# I2C_GPIOs_MIPI-CSI.net
KiCad netlist of a schematic drawn in Altium Designer
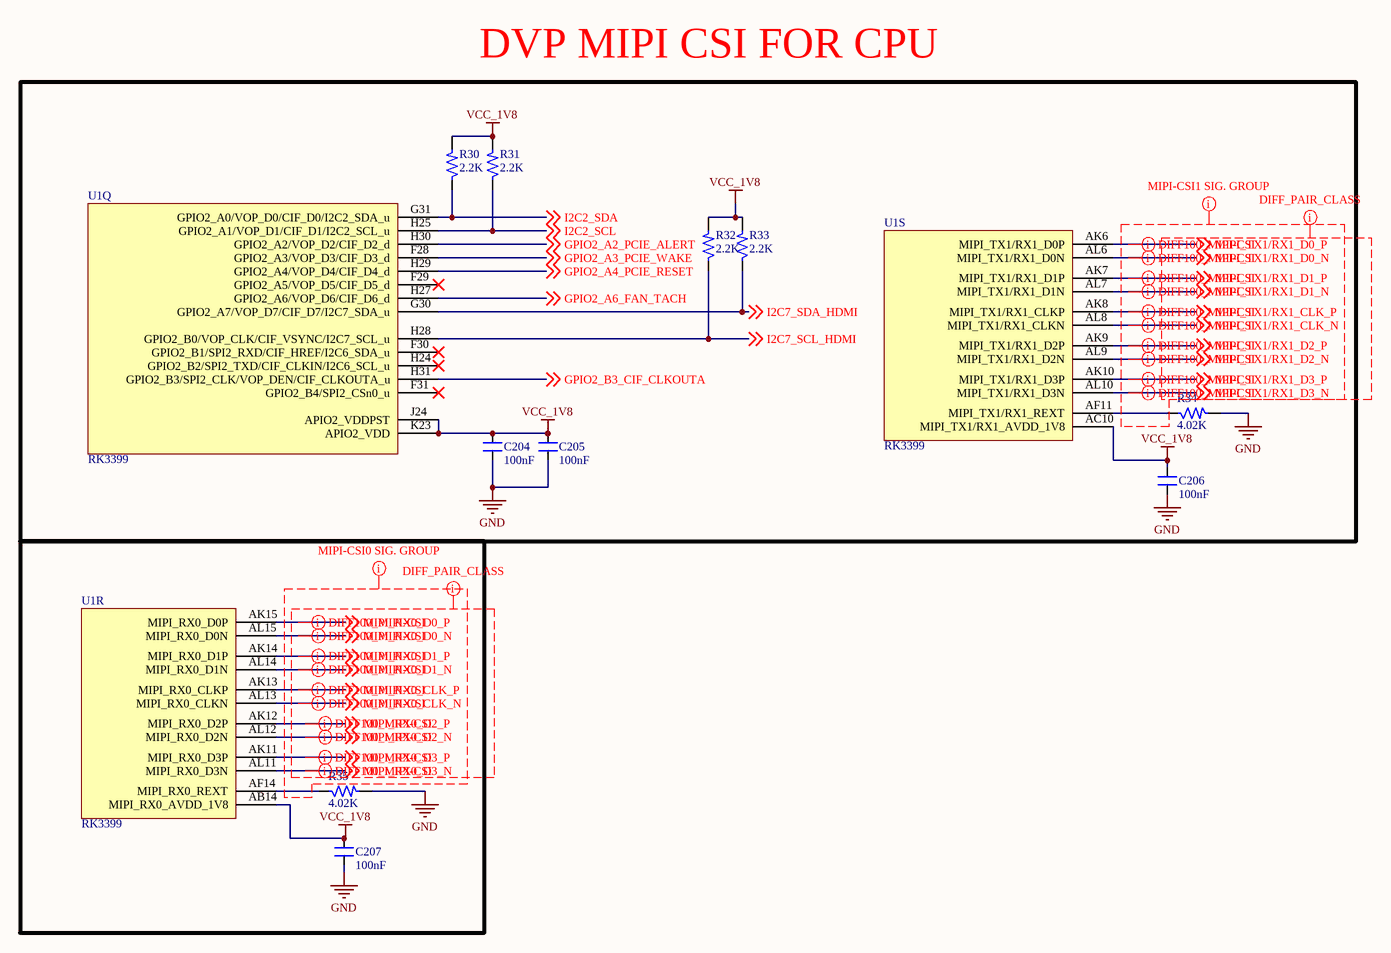
[diagram p0: I2C_GPIOs_MIPI-CSI.SchDoc]

(export (version "E")
  (design (tool "Eeschema 10.0.6"))
  (components
    (comp (ref "C204")
      (value "100nF")
      (footprint "CAP_0201")
      (description "0.1µF ±10% 25V Ceramic Capacitor X5R 0201 (0603 Metric)")
      (fields
        (field (name "MANUFACTURER") "TDK Corporation")
        (field (name "MANUFACTURER PART NUMBER") "C0603X5R1E104K030BB")
      )
      (libsource (lib "RK3399 _Module_Intlib") (part "CAP_100nF-25V-10%-0201"))
    )
    (comp (ref "C205")
      (value "100nF")
      (footprint "CAP_0201")
      (description "0.1µF ±10% 25V Ceramic Capacitor X5R 0201 (0603 Metric)")
      (fields
        (field (name "MANUFACTURER") "TDK Corporation")
        (field (name "MANUFACTURER PART NUMBER") "C0603X5R1E104K030BB")
      )
      (libsource (lib "RK3399 _Module_Intlib") (part "CAP_100nF-25V-10%-0201"))
    )
    (comp (ref "C206")
      (value "100nF")
      (footprint "CAP_0201")
      (description "0.1µF ±10% 25V Ceramic Capacitor X5R 0201 (0603 Metric)")
      (fields
        (field (name "MANUFACTURER") "TDK Corporation")
        (field (name "MANUFACTURER PART NUMBER") "C0603X5R1E104K030BB")
      )
      (libsource (lib "RK3399 _Module_Intlib") (part "CAP_100nF-25V-10%-0201"))
    )
    (comp (ref "C207")
      (value "100nF")
      (footprint "CAP_0201")
      (description "0.1µF ±10% 25V Ceramic Capacitor X5R 0201 (0603 Metric)")
      (fields
        (field (name "MANUFACTURER") "TDK Corporation")
        (field (name "MANUFACTURER PART NUMBER") "C0603X5R1E104K030BB")
      )
      (libsource (lib "RK3399 _Module_Intlib") (part "CAP_100nF-25V-10%-0201"))
    )
    (comp (ref "R30")
      (value "2.2K")
      (footprint "RES_0201")
      (description "2.2 kOhms ±1% 0.05W, 1/20W Chip Resistor 0201 (0603 Metric) Thick Film")
      (fields
        (field (name "MANUFACTURER") "Stackpole Electronics Inc")
        (field (name "MANUFACTURER PART NUMBER") "RMCF0201FT2K20")
      )
      (libsource (lib "RK3399 _Module_Intlib") (part "RES_2.2K-0.05W-1%-0201"))
    )
    (comp (ref "R31")
      (value "2.2K")
      (footprint "RES_0201")
      (description "2.2 kOhms ±1% 0.05W, 1/20W Chip Resistor 0201 (0603 Metric) Thick Film")
      (fields
        (field (name "MANUFACTURER") "Stackpole Electronics Inc")
        (field (name "MANUFACTURER PART NUMBER") "RMCF0201FT2K20")
      )
      (libsource (lib "RK3399 _Module_Intlib") (part "RES_2.2K-0.05W-1%-0201"))
    )
    (comp (ref "R32")
      (value "2.2K")
      (footprint "RES_0201")
      (description "2.2 kOhms ±1% 0.05W, 1/20W Chip Resistor 0201 (0603 Metric) Thick Film")
      (fields
        (field (name "MANUFACTURER") "Stackpole Electronics Inc")
        (field (name "MANUFACTURER PART NUMBER") "RMCF0201FT2K20")
      )
      (libsource (lib "RK3399 _Module_Intlib") (part "RES_2.2K-0.05W-1%-0201"))
    )
    (comp (ref "R33")
      (value "2.2K")
      (footprint "RES_0201")
      (description "2.2 kOhms ±1% 0.05W, 1/20W Chip Resistor 0201 (0603 Metric) Thick Film")
      (fields
        (field (name "MANUFACTURER") "Stackpole Electronics Inc")
        (field (name "MANUFACTURER PART NUMBER") "RMCF0201FT2K20")
      )
      (libsource (lib "RK3399 _Module_Intlib") (part "RES_2.2K-0.05W-1%-0201"))
    )
    (comp (ref "R34")
      (value "4.02K")
      (footprint "RES_0201")
      (description "4.02 kOhms ±1% 0.05W, 1/20W Chip Resistor 0201 (0603 Metric) Thick Film")
      (fields
        (field (name "MANUFACTURER") "Yageo")
        (field (name "MANUFACTURER PART NUMBER") "RC0201FR-074K02L")
      )
      (libsource (lib "RK3399 _Module_Intlib") (part "RES_4.02K-0.05W-1%-0201"))
    )
    (comp (ref "R35")
      (value "4.02K")
      (footprint "RES_0201")
      (description "4.02 kOhms ±1% 0.05W, 1/20W Chip Resistor 0201 (0603 Metric) Thick Film")
      (fields
        (field (name "MANUFACTURER") "Yageo")
        (field (name "MANUFACTURER PART NUMBER") "RC0201FR-074K02L")
      )
      (libsource (lib "RK3399 _Module_Intlib") (part "RES_4.02K-0.05W-1%-0201"))
    )
    (comp (ref "U1")
      (value "RK3399")
      (footprint "FBGA828_23_826X826")
      (description "RK3399 is a low power, high performance processor for computing, personal mobile.")
      (fields (field (name "MANUFACTURER") "Rockchip"))
      (libsource (lib "RK3399 _Module_Schlib") (part "IC_RK3399-FCBGA828"))
    )
  )
  (nets
    (net (code "1") (name "GND") (class "Default")
      (node (ref "C204") (pin "1") (pinfunction "1_1") (pintype "passive"))
      (node (ref "C205") (pin "1") (pinfunction "1_1") (pintype "passive"))
      (node (ref "C206") (pin "1") (pinfunction "1_1") (pintype "passive"))
      (node (ref "C207") (pin "1") (pinfunction "1_1") (pintype "passive"))
      (node (ref "R34") (pin "2") (pinfunction "2_2") (pintype "passive"))
      (node (ref "R35") (pin "2") (pinfunction "2_2") (pintype "passive"))
    )
    (net (code "2") (name "GPIO2_A2_PCIE_ALERT") (class "Default")
      (node (ref "U1") (pin "H30") (pinfunction "GPIO2_A2/VOP_D2/CIF_D2_d_H30") (pintype "passive"))
    )
    (net (code "3") (name "GPIO2_A3_PCIE_WAKE") (class "Default")
      (node (ref "U1") (pin "F28") (pinfunction "GPIO2_A3/VOP_D3/CIF_D3_d_F28") (pintype "passive"))
    )
    (net (code "4") (name "GPIO2_A4_PCIE_RESET") (class "Default")
      (node (ref "U1") (pin "H29") (pinfunction "GPIO2_A4/VOP_D4/CIF_D4_d_H29") (pintype "passive"))
    )
    (net (code "5") (name "GPIO2_A6_FAN_TACH") (class "Default")
      (node (ref "U1") (pin "H27") (pinfunction "GPIO2_A6/VOP_D6/CIF_D6_d_H27") (pintype "passive"))
    )
    (net (code "6") (name "GPIO2_B3_CIF_CLKOUTA") (class "Default")
      (node (ref "U1") (pin "H31") (pinfunction "GPIO2_B3/SPI2_CLK/VOP_DEN/CIF_CLKOUTA_u_H31") (pintype "passive"))
    )
    (net (code "7") (name "I2C2_SCL") (class "Default")
      (node (ref "R31") (pin "1") (pinfunction "1_1") (pintype "passive"))
      (node (ref "U1") (pin "H25") (pinfunction "GPIO2_A1/VOP_D1/CIF_D1/I2C2_SCL_u_H25") (pintype "passive"))
    )
    (net (code "8") (name "I2C2_SDA") (class "Default")
      (node (ref "R30") (pin "1") (pinfunction "1_1") (pintype "passive"))
      (node (ref "U1") (pin "G31") (pinfunction "GPIO2_A0/VOP_D0/CIF_D0/I2C2_SDA_u_G31") (pintype "passive"))
    )
    (net (code "9") (name "I2C7_SCL_HDMI") (class "Default")
      (node (ref "R32") (pin "1") (pinfunction "1_1") (pintype "passive"))
      (node (ref "U1") (pin "H28") (pinfunction "GPIO2_B0/VOP_CLK/CIF_VSYNC/I2C7_SCL_u_H28") (pintype "passive"))
    )
    (net (code "10") (name "I2C7_SDA_HDMI") (class "Default")
      (node (ref "R33") (pin "1") (pinfunction "1_1") (pintype "passive"))
      (node (ref "U1") (pin "G30") (pinfunction "GPIO2_A7/VOP_D7/CIF_D7/I2C7_SDA_u_G30") (pintype "passive"))
    )
    (net (code "11") (name "MIPI_RX0_CLK_N") (class "Default")
      (node (ref "U1") (pin "AL13") (pinfunction "MIPI_RX0_CLKN_AL13") (pintype "passive"))
    )
    (net (code "12") (name "MIPI_RX0_CLK_P") (class "Default")
      (node (ref "U1") (pin "AK13") (pinfunction "MIPI_RX0_CLKP_AK13") (pintype "passive"))
    )
    (net (code "13") (name "MIPI_RX0_D0_N") (class "Default")
      (node (ref "U1") (pin "AL15") (pinfunction "MIPI_RX0_D0N_AL15") (pintype "passive"))
    )
    (net (code "14") (name "MIPI_RX0_D0_P") (class "Default")
      (node (ref "U1") (pin "AK15") (pinfunction "MIPI_RX0_D0P_AK15") (pintype "passive"))
    )
    (net (code "15") (name "MIPI_RX0_D1_N") (class "Default")
      (node (ref "U1") (pin "AL14") (pinfunction "MIPI_RX0_D1N_AL14") (pintype "passive"))
    )
    (net (code "16") (name "MIPI_RX0_D1_P") (class "Default")
      (node (ref "U1") (pin "AK14") (pinfunction "MIPI_RX0_D1P_AK14") (pintype "passive"))
    )
    (net (code "17") (name "MIPI_RX0_D2_N") (class "Default")
      (node (ref "U1") (pin "AL12") (pinfunction "MIPI_RX0_D2N_AL12") (pintype "passive"))
    )
    (net (code "18") (name "MIPI_RX0_D2_P") (class "Default")
      (node (ref "U1") (pin "AK12") (pinfunction "MIPI_RX0_D2P_AK12") (pintype "passive"))
    )
    (net (code "19") (name "MIPI_RX0_D3_N") (class "Default")
      (node (ref "U1") (pin "AL11") (pinfunction "MIPI_RX0_D3N_AL11") (pintype "passive"))
    )
    (net (code "20") (name "MIPI_RX0_D3_P") (class "Default")
      (node (ref "U1") (pin "AK11") (pinfunction "MIPI_RX0_D3P_AK11") (pintype "passive"))
    )
    (net (code "21") (name "MIPI_TX1{slash}RX1_CLK_N") (class "Default")
      (node (ref "U1") (pin "AL8") (pinfunction "MIPI_TX1/RX1_CLKN_AL8") (pintype "passive"))
    )
    (net (code "22") (name "MIPI_TX1{slash}RX1_CLK_P") (class "Default")
      (node (ref "U1") (pin "AK8") (pinfunction "MIPI_TX1/RX1_CLKP_AK8") (pintype "passive"))
    )
    (net (code "23") (name "MIPI_TX1{slash}RX1_D0_N") (class "Default")
      (node (ref "U1") (pin "AL6") (pinfunction "MIPI_TX1/RX1_D0N_AL6") (pintype "passive"))
    )
    (net (code "24") (name "MIPI_TX1{slash}RX1_D0_P") (class "Default")
      (node (ref "U1") (pin "AK6") (pinfunction "MIPI_TX1/RX1_D0P_AK6") (pintype "passive"))
    )
    (net (code "25") (name "MIPI_TX1{slash}RX1_D1_N") (class "Default")
      (node (ref "U1") (pin "AL7") (pinfunction "MIPI_TX1/RX1_D1N_AL7") (pintype "passive"))
    )
    (net (code "26") (name "MIPI_TX1{slash}RX1_D1_P") (class "Default")
      (node (ref "U1") (pin "AK7") (pinfunction "MIPI_TX1/RX1_D1P_AK7") (pintype "passive"))
    )
    (net (code "27") (name "MIPI_TX1{slash}RX1_D2_N") (class "Default")
      (node (ref "U1") (pin "AL9") (pinfunction "MIPI_TX1/RX1_D2N_AL9") (pintype "passive"))
    )
    (net (code "28") (name "MIPI_TX1{slash}RX1_D2_P") (class "Default")
      (node (ref "U1") (pin "AK9") (pinfunction "MIPI_TX1/RX1_D2P_AK9") (pintype "passive"))
    )
    (net (code "29") (name "MIPI_TX1{slash}RX1_D3_N") (class "Default")
      (node (ref "U1") (pin "AL10") (pinfunction "MIPI_TX1/RX1_D3N_AL10") (pintype "passive"))
    )
    (net (code "30") (name "MIPI_TX1{slash}RX1_D3_P") (class "Default")
      (node (ref "U1") (pin "AK10") (pinfunction "MIPI_TX1/RX1_D3P_AK10") (pintype "passive"))
    )
    (net (code "31") (name "Net-(U1R-MIPI_RX0_REXT)") (class "Default")
      (node (ref "R35") (pin "1") (pinfunction "1_1") (pintype "passive"))
      (node (ref "U1") (pin "AF14") (pinfunction "MIPI_RX0_REXT_AF14") (pintype "passive"))
    )
    (net (code "32") (name "Net-(U1S-MIPI_TX1{slash}RX1_REXT)") (class "Default")
      (node (ref "R34") (pin "1") (pinfunction "1_1") (pintype "passive"))
      (node (ref "U1") (pin "AF11") (pinfunction "MIPI_TX1/RX1_REXT_AF11") (pintype "passive"))
    )
    (net (code "33") (name "VCC_1V8") (class "Default")
      (node (ref "C204") (pin "2") (pinfunction "2_2") (pintype "passive"))
      (node (ref "C205") (pin "2") (pinfunction "2_2") (pintype "passive"))
      (node (ref "C206") (pin "2") (pinfunction "2_2") (pintype "passive"))
      (node (ref "C207") (pin "2") (pinfunction "2_2") (pintype "passive"))
      (node (ref "R30") (pin "2") (pinfunction "2_2") (pintype "passive"))
      (node (ref "R31") (pin "2") (pinfunction "2_2") (pintype "passive"))
      (node (ref "R32") (pin "2") (pinfunction "2_2") (pintype "passive"))
      (node (ref "R33") (pin "2") (pinfunction "2_2") (pintype "passive"))
      (node (ref "U1") (pin "AB14") (pinfunction "MIPI_RX0_AVDD_1V8_AB14") (pintype "passive"))
      (node (ref "U1") (pin "AC10") (pinfunction "MIPI_TX1/RX1_AVDD_1V8_AC10") (pintype "passive"))
      (node (ref "U1") (pin "J24") (pinfunction "APIO2_VDDPST_J24") (pintype "passive"))
      (node (ref "U1") (pin "K23") (pinfunction "APIO2_VDD_K23") (pintype "passive"))
    )
    (net (code "34") (name "unconnected-(U1Q-GPIO2_A5{slash}VOP_D5{slash}CIF_D5_d-PadF29)") (class "Default")
      (node (ref "U1") (pin "F29") (pinfunction "GPIO2_A5/VOP_D5/CIF_D5_d_F29") (pintype "passive+no_connect"))
    )
    (net (code "35") (name "unconnected-(U1Q-GPIO2_B1{slash}SPI2_RXD{slash}CIF_HREF{slash}I2C6_SDA_u-PadF30)") (class "Default")
      (node (ref "U1") (pin "F30") (pinfunction "GPIO2_B1/SPI2_RXD/CIF_HREF/I2C6_SDA_u_F30") (pintype "passive+no_connect"))
    )
    (net (code "36") (name "unconnected-(U1Q-GPIO2_B2{slash}SPI2_TXD{slash}CIF_CLKIN{slash}I2C6_SCL_u-PadH24)") (class "Default")
      (node (ref "U1") (pin "H24") (pinfunction "GPIO2_B2/SPI2_TXD/CIF_CLKIN/I2C6_SCL_u_H24") (pintype "passive+no_connect"))
    )
    (net (code "37") (name "unconnected-(U1Q-GPIO2_B4{slash}SPI2_CSn0_u-PadF31)") (class "Default")
      (node (ref "U1") (pin "F31") (pinfunction "GPIO2_B4/SPI2_CSn0_u_F31") (pintype "passive+no_connect"))
    )
  )
)
